# 0_Overview.net
KiCad netlist of a schematic drawn in Altium Designer
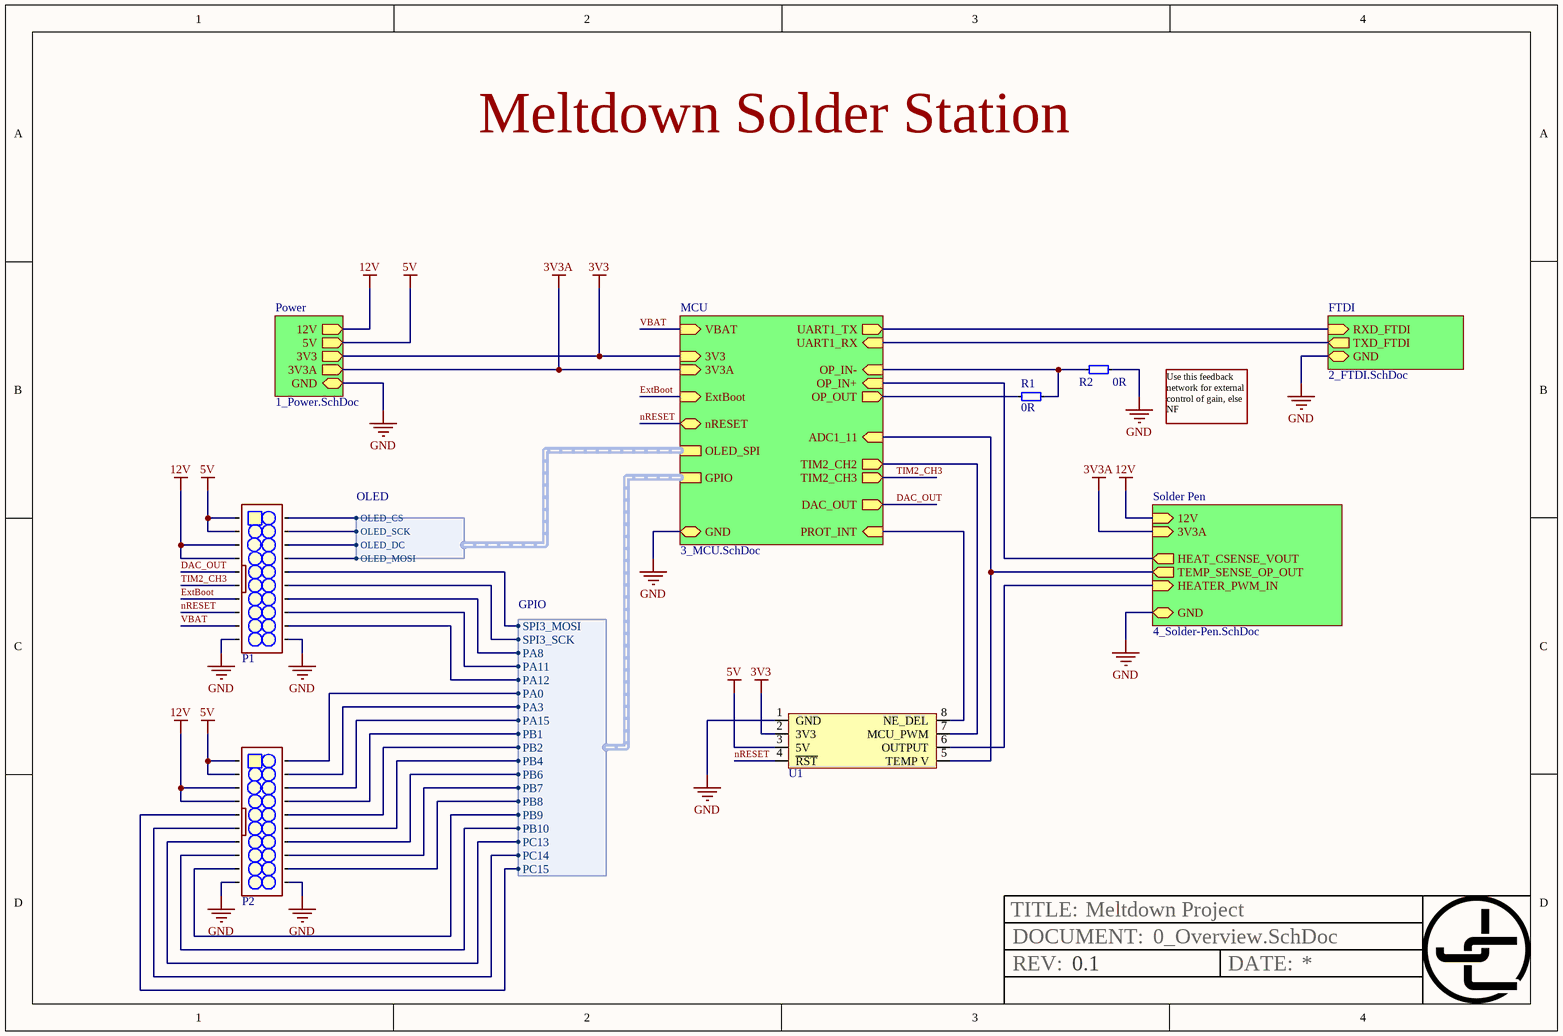
[diagram p0: 0_Overview.SchDoc]

(export (version "E")
  (design (tool "Eeschema 10.0.6"))
  (components
    (comp (ref "P1")
      (value "2x10 Ribbon Header")
      (footprint "2x10_RIBBON_CABLE_CON")
      (description "2.54 mm")
      (libsource (lib "jclib") (part "2x10 Ribbon Header"))
    )
    (comp (ref "P2")
      (value "2x10 Ribbon Header")
      (footprint "2x10_RIBBON_CABLE_CON")
      (description "2.54 mm")
      (libsource (lib "jclib") (part "2x10 Ribbon Header"))
    )
    (comp (ref "R1")
      (value "0R")
      (footprint "0603")
      (fields (field (name "Comment") "0603, resistor"))
      (libsource (lib "jclib") (part "0603, resistor"))
    )
    (comp (ref "R2")
      (value "0R")
      (footprint "0603")
      (fields (field (name "Comment") "0603, resistor"))
      (libsource (lib "jclib") (part "0603, resistor"))
    )
    (comp (ref "U1")
      (value "Meltdown Protection Module")
      (footprint "MELTDOWN_PROT")
      (description "Protection circuit for the meltdown project")
      (libsource (lib "jclib") (part "Meltdown Protection Module"))
    )
  )
  (nets
    (net (code "3") (name "/DAC_OUT") (class "Default")
      (node (ref "P1") (pin "5") (pinfunction "5_5") (pintype "passive"))
    )
    (net (code "4") (name "/ExtBoot") (class "Default")
      (node (ref "P1") (pin "7") (pinfunction "7_7") (pintype "passive"))
    )
    (net (code "5") (name "/HEATER_PWM_IN") (class "Default")
      (node (ref "U1") (pin "6") (pinfunction "OUTPUT_6") (pintype "passive"))
    )
    (net (code "7") (name "/OLED_CS") (class "Default")
      (node (ref "P1") (pin "20") (pinfunction "20_20") (pintype "passive"))
    )
    (net (code "8") (name "/OLED_DC") (class "Default")
      (node (ref "P1") (pin "18") (pinfunction "18_18") (pintype "passive"))
    )
    (net (code "9") (name "/OLED_MOSI") (class "Default")
      (node (ref "P1") (pin "17") (pinfunction "17_17") (pintype "passive"))
    )
    (net (code "10") (name "/OLED_SCK") (class "Default")
      (node (ref "P1") (pin "19") (pinfunction "19_19") (pintype "passive"))
    )
    (net (code "11") (name "/OP_IN-") (class "Default")
      (node (ref "R1") (pin "1") (pinfunction "1_1") (pintype "passive"))
      (node (ref "R2") (pin "1") (pinfunction "1_1") (pintype "passive"))
    )
    (net (code "12") (name "/OP_OUT") (class "Default")
      (node (ref "R1") (pin "0") (pinfunction "0_0") (pintype "passive"))
    )
    (net (code "13") (name "/PA0") (class "Default")
      (node (ref "P2") (pin "20") (pinfunction "20_20") (pintype "passive"))
    )
    (net (code "14") (name "/PA3") (class "Default")
      (node (ref "P2") (pin "19") (pinfunction "19_19") (pintype "passive"))
    )
    (net (code "15") (name "/PA8") (class "Default")
      (node (ref "P1") (pin "14") (pinfunction "14_14") (pintype "passive"))
    )
    (net (code "16") (name "/PA11") (class "Default")
      (node (ref "P1") (pin "13") (pinfunction "13_13") (pintype "passive"))
    )
    (net (code "17") (name "/PA12") (class "Default")
      (node (ref "P1") (pin "12") (pinfunction "12_12") (pintype "passive"))
    )
    (net (code "18") (name "/PA15") (class "Default")
      (node (ref "P2") (pin "18") (pinfunction "18_18") (pintype "passive"))
    )
    (net (code "19") (name "/PB1") (class "Default")
      (node (ref "P2") (pin "17") (pinfunction "17_17") (pintype "passive"))
    )
    (net (code "20") (name "/PB2") (class "Default")
      (node (ref "P2") (pin "16") (pinfunction "16_16") (pintype "passive"))
    )
    (net (code "21") (name "/PB4") (class "Default")
      (node (ref "P2") (pin "15") (pinfunction "15_15") (pintype "passive"))
    )
    (net (code "22") (name "/PB6") (class "Default")
      (node (ref "P2") (pin "14") (pinfunction "14_14") (pintype "passive"))
    )
    (net (code "23") (name "/PB7") (class "Default")
      (node (ref "P2") (pin "13") (pinfunction "13_13") (pintype "passive"))
    )
    (net (code "24") (name "/PB8") (class "Default")
      (node (ref "P2") (pin "12") (pinfunction "12_12") (pintype "passive"))
    )
    (net (code "25") (name "/PB9") (class "Default")
      (node (ref "P2") (pin "9") (pinfunction "9_9") (pintype "passive"))
    )
    (net (code "26") (name "/PB10") (class "Default")
      (node (ref "P2") (pin "8") (pinfunction "8_8") (pintype "passive"))
    )
    (net (code "27") (name "/PC13") (class "Default")
      (node (ref "P2") (pin "7") (pinfunction "7_7") (pintype "passive"))
    )
    (net (code "28") (name "/PC14") (class "Default")
      (node (ref "P2") (pin "6") (pinfunction "6_6") (pintype "passive"))
    )
    (net (code "29") (name "/PC15") (class "Default")
      (node (ref "P2") (pin "5") (pinfunction "5_5") (pintype "passive"))
    )
    (net (code "30") (name "/PROT_INT") (class "Default")
      (node (ref "U1") (pin "8") (pinfunction "NE_DEL_8") (pintype "passive"))
    )
    (net (code "31") (name "/SPI3_MOSI") (class "Default")
      (node (ref "P1") (pin "16") (pinfunction "16_16") (pintype "passive"))
    )
    (net (code "32") (name "/SPI3_SCK") (class "Default")
      (node (ref "P1") (pin "15") (pinfunction "15_15") (pintype "passive"))
    )
    (net (code "33") (name "/TEMP_SENSE_OP_OUT") (class "Default")
      (node (ref "U1") (pin "5") (pinfunction "TEMP_V_5") (pintype "passive"))
    )
    (net (code "34") (name "/TIM2_CH2") (class "Default")
      (node (ref "U1") (pin "7") (pinfunction "MCU_PWM_7") (pintype "passive"))
    )
    (net (code "35") (name "/TIM2_CH3") (class "Default")
      (node (ref "P1") (pin "6") (pinfunction "6_6") (pintype "passive"))
    )
    (net (code "38") (name "/VBAT") (class "Default")
      (node (ref "P1") (pin "9") (pinfunction "9_9") (pintype "passive"))
    )
    (net (code "39") (name "/nRESET") (class "Default")
      (node (ref "P1") (pin "8") (pinfunction "8_8") (pintype "passive"))
      (node (ref "U1") (pin "4") (pinfunction "~{RST}_4") (pintype "passive"))
    )
    (net (code "42") (name "3V3") (class "Default")
      (node (ref "U1") (pin "2") (pinfunction "3V3_2") (pintype "passive"))
    )
    (net (code "44") (name "5V") (class "Default")
      (node (ref "P1") (pin "1") (pinfunction "1_1") (pintype "passive"))
      (node (ref "P1") (pin "2") (pinfunction "2_2") (pintype "passive"))
      (node (ref "P2") (pin "1") (pinfunction "1_1") (pintype "passive"))
      (node (ref "P2") (pin "2") (pinfunction "2_2") (pintype "passive"))
      (node (ref "U1") (pin "3") (pinfunction "5V_3") (pintype "passive"))
    )
    (net (code "45") (name "12V") (class "Default")
      (node (ref "P1") (pin "3") (pinfunction "3_3") (pintype "passive"))
      (node (ref "P1") (pin "4") (pinfunction "4_4") (pintype "passive"))
      (node (ref "P2") (pin "3") (pinfunction "3_3") (pintype "passive"))
      (node (ref "P2") (pin "4") (pinfunction "4_4") (pintype "passive"))
    )
    (net (code "46") (name "GND") (class "Default")
      (node (ref "P1") (pin "10") (pinfunction "10_10") (pintype "passive"))
      (node (ref "P1") (pin "11") (pinfunction "11_11") (pintype "passive"))
      (node (ref "P2") (pin "10") (pinfunction "10_10") (pintype "passive"))
      (node (ref "P2") (pin "11") (pinfunction "11_11") (pintype "passive"))
      (node (ref "R2") (pin "0") (pinfunction "0_0") (pintype "passive"))
      (node (ref "U1") (pin "1") (pinfunction "GND_1") (pintype "passive"))
    )
  )
)
